# pcf8574_lcd_hw1_0.net
KiCad netlist of a schematic drawn in EAGLE
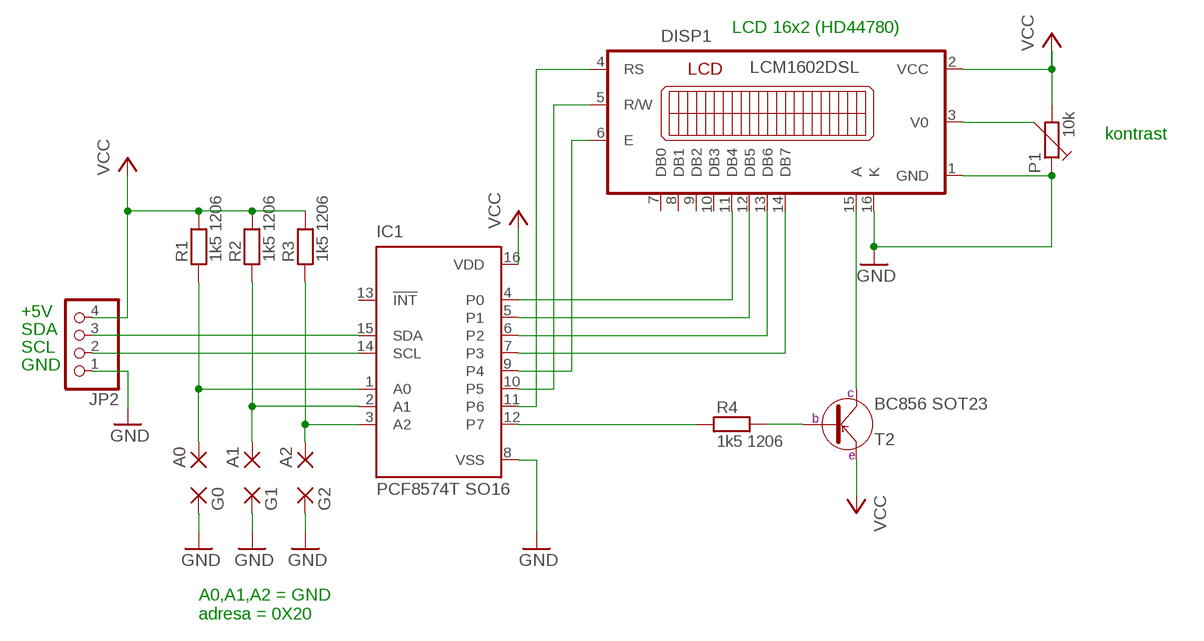
[diagram p0: schematic, sheet 1]

(export (version "E")
  (design (tool "Eeschema 10.0.6"))
  (components
    (comp (ref "A0")
      (value "SMD2")
      (footprint "eagle-import:SMD1,27-2,54")
      (libsource (lib "eagle-import") (part "SMD2"))
    )
    (comp (ref "A1")
      (value "SMD2")
      (footprint "eagle-import:SMD1,27-2,54")
      (libsource (lib "eagle-import") (part "SMD2"))
    )
    (comp (ref "A2")
      (value "SMD2")
      (footprint "eagle-import:SMD1,27-2,54")
      (libsource (lib "eagle-import") (part "SMD2"))
    )
    (comp (ref "DISP1")
      (value "LCM1602DSL")
      (footprint "eagle-import:LCM1602DSL")
      (libsource (lib "eagle-import") (part "LCM1602DSL"))
    )
    (comp (ref "G0")
      (value "SMD2")
      (footprint "eagle-import:SMD1,27-2,54")
      (libsource (lib "eagle-import") (part "SMD2"))
    )
    (comp (ref "G1")
      (value "SMD2")
      (footprint "eagle-import:SMD1,27-2,54")
      (libsource (lib "eagle-import") (part "SMD2"))
    )
    (comp (ref "G2")
      (value "SMD2")
      (footprint "eagle-import:SMD1,27-2,54")
      (libsource (lib "eagle-import") (part "SMD2"))
    )
    (comp (ref "IC1")
      (value "PCF8574T SO16")
      (footprint "eagle-import:SO16W")
      (fields (field (name "MPN") "PCF8574T/3,512"))
      (libsource (lib "eagle-import") (part "PCF8574T"))
    )
    (comp (ref "JP2")
      (value "PINHD-1X4")
      (footprint "eagle-import:1X04")
      (libsource (lib "eagle-import") (part "PINHD-1X4"))
    )
    (comp (ref "P1")
      (value "10k")
      (footprint "eagle-import:PT10V")
      (libsource (lib "eagle-import") (part "TRIMRPT10V"))
    )
    (comp (ref "R1")
      (value "1k5 1206")
      (footprint "eagle-import:1206")
      (libsource (lib "eagle-import") (part "R_1206"))
    )
    (comp (ref "R2")
      (value "1k5 1206")
      (footprint "eagle-import:1206")
      (libsource (lib "eagle-import") (part "R_1206"))
    )
    (comp (ref "R3")
      (value "1k5 1206")
      (footprint "eagle-import:1206")
      (libsource (lib "eagle-import") (part "R_1206"))
    )
    (comp (ref "R4")
      (value "1k5 1206")
      (footprint "eagle-import:1206")
      (libsource (lib "eagle-import") (part "R_1206"))
    )
    (comp (ref "T2")
      (value "BC856 SOT23")
      (footprint "eagle-import:SOT-23")
      (libsource (lib "eagle-import") (part "BC856"))
    )
  )
  (nets
    (net (code "1") (name "GND") (class "Default")
      (node (ref "DISP1") (pin "1") (pinfunction "GND_1") (pintype "power_in"))
      (node (ref "DISP1") (pin "16") (pinfunction "K_16") (pintype "passive"))
      (node (ref "G0") (pin "1") (pinfunction "P_1") (pintype "passive"))
      (node (ref "G1") (pin "1") (pinfunction "P_1") (pintype "passive"))
      (node (ref "G2") (pin "1") (pinfunction "P_1") (pintype "passive"))
      (node (ref "IC1") (pin "8") (pinfunction "VSS_8") (pintype "power_in"))
      (node (ref "JP2") (pin "1") (pinfunction "1_1") (pintype "passive"))
      (node (ref "P1") (pin "1") (pinfunction "1_1") (pintype "passive"))
    )
    (net (code "2") (name "Net-(A0-P)") (class "Default")
      (node (ref "A0") (pin "1") (pinfunction "P_1") (pintype "passive"))
      (node (ref "IC1") (pin "1") (pinfunction "A0_1") (pintype "input"))
      (node (ref "R1") (pin "1") (pinfunction "1_1") (pintype "passive"))
    )
    (net (code "3") (name "Net-(A1-P)") (class "Default")
      (node (ref "A1") (pin "1") (pinfunction "P_1") (pintype "passive"))
      (node (ref "IC1") (pin "2") (pinfunction "A1_2") (pintype "input"))
      (node (ref "R2") (pin "1") (pinfunction "1_1") (pintype "passive"))
    )
    (net (code "4") (name "Net-(A2-P)") (class "Default")
      (node (ref "A2") (pin "1") (pinfunction "P_1") (pintype "passive"))
      (node (ref "IC1") (pin "3") (pinfunction "A2_3") (pintype "input"))
      (node (ref "R3") (pin "1") (pinfunction "1_1") (pintype "passive"))
    )
    (net (code "5") (name "Net-(DISP1-A)") (class "Default")
      (node (ref "DISP1") (pin "15") (pinfunction "A_15") (pintype "passive"))
      (node (ref "T2") (pin "3") (pinfunction "C_3") (pintype "passive"))
    )
    (net (code "6") (name "Net-(DISP1-DB4)") (class "Default")
      (node (ref "DISP1") (pin "11") (pinfunction "DB4_11") (pintype "passive"))
      (node (ref "IC1") (pin "4") (pinfunction "P0_4") (pintype "bidirectional"))
    )
    (net (code "7") (name "Net-(DISP1-DB5)") (class "Default")
      (node (ref "DISP1") (pin "12") (pinfunction "DB5_12") (pintype "passive"))
      (node (ref "IC1") (pin "5") (pinfunction "P1_5") (pintype "bidirectional"))
    )
    (net (code "8") (name "Net-(DISP1-DB6)") (class "Default")
      (node (ref "DISP1") (pin "13") (pinfunction "DB6_13") (pintype "passive"))
      (node (ref "IC1") (pin "6") (pinfunction "P2_6") (pintype "bidirectional"))
    )
    (net (code "9") (name "Net-(DISP1-DB7)") (class "Default")
      (node (ref "DISP1") (pin "14") (pinfunction "DB7_14") (pintype "passive"))
      (node (ref "IC1") (pin "7") (pinfunction "P3_7") (pintype "bidirectional"))
    )
    (net (code "10") (name "Net-(DISP1-E)") (class "Default")
      (node (ref "DISP1") (pin "6") (pinfunction "E_6") (pintype "input"))
      (node (ref "IC1") (pin "9") (pinfunction "P4_9") (pintype "bidirectional"))
    )
    (net (code "11") (name "Net-(DISP1-RS)") (class "Default")
      (node (ref "DISP1") (pin "4") (pinfunction "RS_4") (pintype "input"))
      (node (ref "IC1") (pin "11") (pinfunction "P6_11") (pintype "bidirectional"))
    )
    (net (code "12") (name "Net-(DISP1-R{slash}W)") (class "Default")
      (node (ref "DISP1") (pin "5") (pinfunction "R/W_5") (pintype "input"))
      (node (ref "IC1") (pin "10") (pinfunction "P5_10") (pintype "bidirectional"))
    )
    (net (code "13") (name "Net-(DISP1-V0)") (class "Default")
      (node (ref "DISP1") (pin "3") (pinfunction "V0_3") (pintype "power_in"))
      (node (ref "P1") (pin "3") (pinfunction "3_3") (pintype "passive"))
    )
    (net (code "14") (name "Net-(IC1-P7)") (class "Default")
      (node (ref "IC1") (pin "12") (pinfunction "P7_12") (pintype "bidirectional"))
      (node (ref "R4") (pin "1") (pinfunction "1_1") (pintype "passive"))
    )
    (net (code "15") (name "Net-(IC1-SCL)") (class "Default")
      (node (ref "IC1") (pin "14") (pinfunction "SCL_14") (pintype "input"))
      (node (ref "JP2") (pin "2") (pinfunction "2_2") (pintype "passive"))
    )
    (net (code "16") (name "Net-(IC1-SDA)") (class "Default")
      (node (ref "IC1") (pin "15") (pinfunction "SDA_15") (pintype "bidirectional"))
      (node (ref "JP2") (pin "3") (pinfunction "3_3") (pintype "passive"))
    )
    (net (code "17") (name "Net-(T2-B)") (class "Default")
      (node (ref "R4") (pin "2") (pinfunction "2_2") (pintype "passive"))
      (node (ref "T2") (pin "1") (pinfunction "B_1") (pintype "passive"))
    )
    (net (code "18") (name "VCC") (class "Default")
      (node (ref "DISP1") (pin "2") (pinfunction "VCC_2") (pintype "power_in"))
      (node (ref "IC1") (pin "16") (pinfunction "VDD_16") (pintype "power_in"))
      (node (ref "JP2") (pin "4") (pinfunction "4_4") (pintype "passive"))
      (node (ref "P1") (pin "2") (pinfunction "2_2") (pintype "passive"))
      (node (ref "R1") (pin "2") (pinfunction "2_2") (pintype "passive"))
      (node (ref "R2") (pin "2") (pinfunction "2_2") (pintype "passive"))
      (node (ref "R3") (pin "2") (pinfunction "2_2") (pintype "passive"))
      (node (ref "T2") (pin "2") (pinfunction "E_2") (pintype "passive"))
    )
    (net (code "19") (name "unconnected-(DISP1-DB0-Pad7)") (class "Default")
      (node (ref "DISP1") (pin "7") (pinfunction "DB0_7") (pintype "passive"))
    )
    (net (code "20") (name "unconnected-(DISP1-DB1-Pad8)") (class "Default")
      (node (ref "DISP1") (pin "8") (pinfunction "DB1_8") (pintype "passive"))
    )
    (net (code "21") (name "unconnected-(DISP1-DB2-Pad9)") (class "Default")
      (node (ref "DISP1") (pin "9") (pinfunction "DB2_9") (pintype "passive"))
    )
    (net (code "22") (name "unconnected-(DISP1-DB3-Pad10)") (class "Default")
      (node (ref "DISP1") (pin "10") (pinfunction "DB3_10") (pintype "passive"))
    )
    (net (code "23") (name "unconnected-(IC1-~{INT}-Pad13)") (class "Default")
      (node (ref "IC1") (pin "13") (pinfunction "~{INT}_13") (pintype "output"))
    )
  )
)
